# core09e.net
KiCad netlist of a schematic drawn in EAGLE
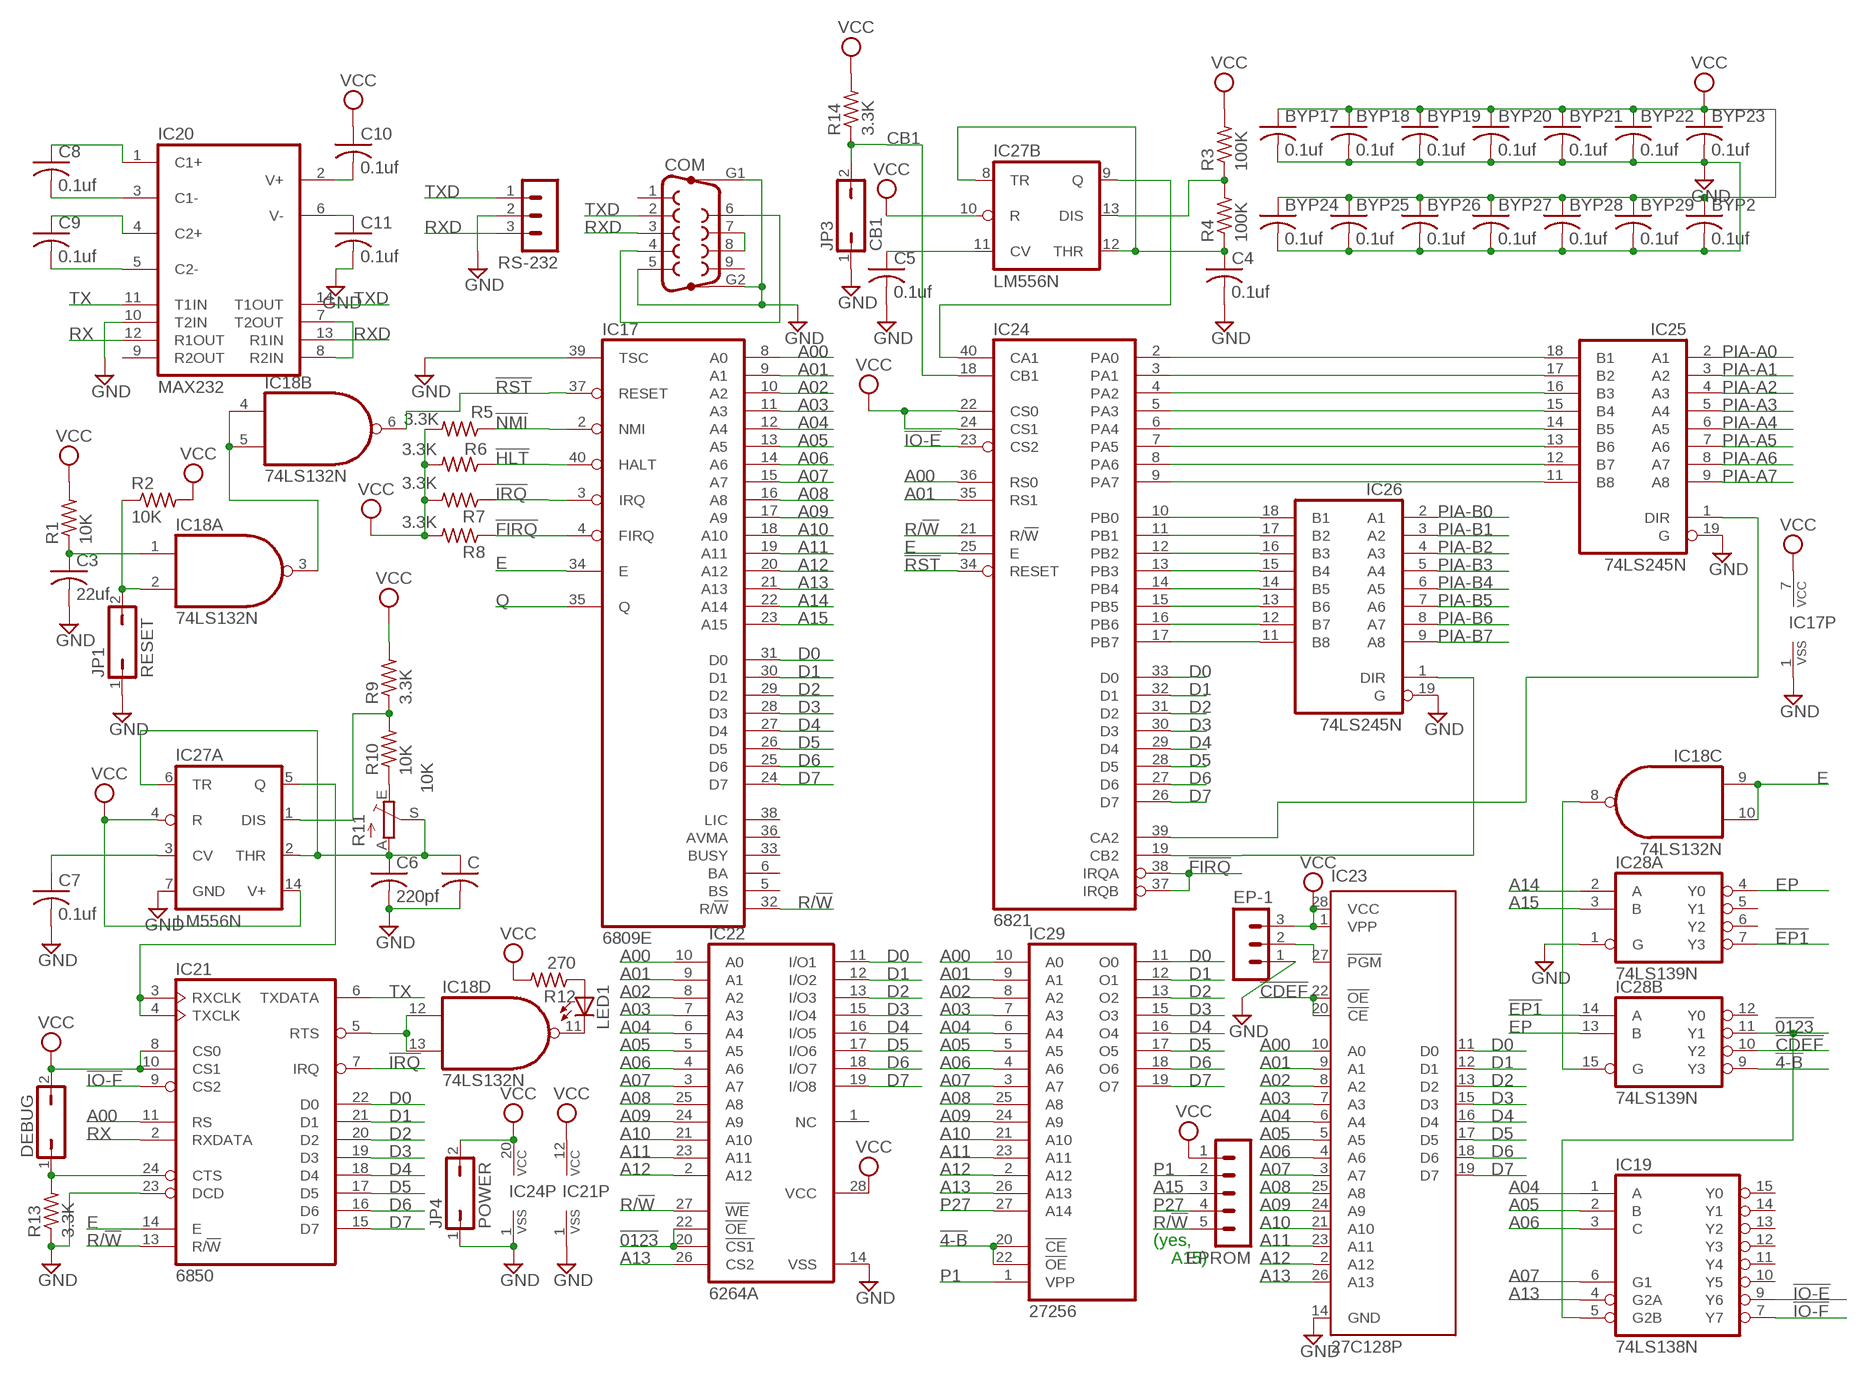
[diagram p0: schematic, sheet 1]
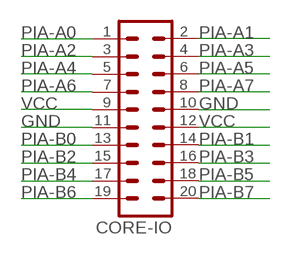
[diagram p1: schematic, sheet 2]
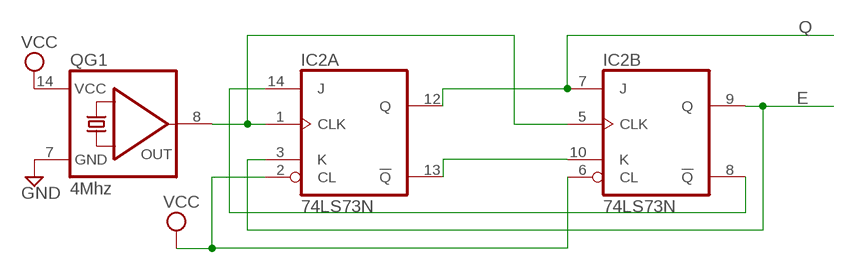
[diagram p2: schematic, sheet 3]

(export (version "E")
  (design (tool "Eeschema 10.0.6"))
  (components
    (comp (ref "IC2")
      (value "74LS73N")
      (footprint "eagle-import:DIL14")
      (libsource (lib "eagle-import") (part "7473NLS"))
    )
    (comp (ref "QG1")
      (value "4Mhz")
      (footprint "eagle-import:DIL14S")
      (libsource (lib "eagle-import") (part "QG5860"))
    )
    (comp (ref "BYP2")
      (value "0.1uf")
      (footprint "eagle-import:C050-025X075")
      (libsource (lib "eagle-import") (part "C-US050-025X075"))
    )
    (comp (ref "BYP17")
      (value "0.1uf")
      (footprint "eagle-import:C050-025X075")
      (libsource (lib "eagle-import") (part "C-US050-025X075"))
    )
    (comp (ref "BYP18")
      (value "0.1uf")
      (footprint "eagle-import:C050-025X075")
      (libsource (lib "eagle-import") (part "C-US050-025X075"))
    )
    (comp (ref "BYP19")
      (value "0.1uf")
      (footprint "eagle-import:C050-025X075")
      (libsource (lib "eagle-import") (part "C-US050-025X075"))
    )
    (comp (ref "BYP20")
      (value "0.1uf")
      (footprint "eagle-import:C050-025X075")
      (libsource (lib "eagle-import") (part "C-US050-025X075"))
    )
    (comp (ref "BYP21")
      (value "0.1uf")
      (footprint "eagle-import:C050-025X075")
      (libsource (lib "eagle-import") (part "C-US050-025X075"))
    )
    (comp (ref "BYP22")
      (value "0.1uf")
      (footprint "eagle-import:C050-025X075")
      (libsource (lib "eagle-import") (part "C-US050-025X075"))
    )
    (comp (ref "BYP23")
      (value "0.1uf")
      (footprint "eagle-import:C050-025X075")
      (libsource (lib "eagle-import") (part "C-US050-025X075"))
    )
    (comp (ref "BYP24")
      (value "0.1uf")
      (footprint "eagle-import:C050-025X075")
      (libsource (lib "eagle-import") (part "C-US050-025X075"))
    )
    (comp (ref "BYP25")
      (value "0.1uf")
      (footprint "eagle-import:C050-025X075")
      (libsource (lib "eagle-import") (part "C-US050-025X075"))
    )
    (comp (ref "BYP26")
      (value "0.1uf")
      (footprint "eagle-import:C050-025X075")
      (libsource (lib "eagle-import") (part "C-US050-025X075"))
    )
    (comp (ref "BYP27")
      (value "0.1uf")
      (footprint "eagle-import:C050-025X075")
      (libsource (lib "eagle-import") (part "C-US050-025X075"))
    )
    (comp (ref "BYP28")
      (value "0.1uf")
      (footprint "eagle-import:C050-025X075")
      (libsource (lib "eagle-import") (part "C-US050-025X075"))
    )
    (comp (ref "BYP29")
      (value "0.1uf")
      (footprint "eagle-import:C050-025X075")
      (libsource (lib "eagle-import") (part "C-US050-025X075"))
    )
    (comp (ref "C")
      (value "C-US050-025X075")
      (footprint "eagle-import:C050-025X075")
      (libsource (lib "eagle-import") (part "C-US050-025X075"))
    )
    (comp (ref "C3")
      (value "22uf")
      (footprint "eagle-import:C102-054X133")
      (libsource (lib "eagle-import") (part "C-US102-054X133"))
    )
    (comp (ref "C4")
      (value "0.1uf")
      (footprint "eagle-import:C050-025X075")
      (libsource (lib "eagle-import") (part "C-US050-025X075"))
    )
    (comp (ref "C5")
      (value "0.1uf")
      (footprint "eagle-import:C050-025X075")
      (libsource (lib "eagle-import") (part "C-US050-025X075"))
    )
    (comp (ref "C6")
      (value "220pf")
      (footprint "eagle-import:C050-025X075")
      (libsource (lib "eagle-import") (part "C-US050-025X075"))
    )
    (comp (ref "C7")
      (value "0.1uf")
      (footprint "eagle-import:C050-025X075")
      (libsource (lib "eagle-import") (part "C-US050-025X075"))
    )
    (comp (ref "C8")
      (value "0.1uf")
      (footprint "eagle-import:C050-025X075")
      (libsource (lib "eagle-import") (part "C-US050-025X075"))
    )
    (comp (ref "C9")
      (value "0.1uf")
      (footprint "eagle-import:C050-025X075")
      (libsource (lib "eagle-import") (part "C-US050-025X075"))
    )
    (comp (ref "C10")
      (value "0.1uf")
      (footprint "eagle-import:C050-025X075")
      (libsource (lib "eagle-import") (part "C-US050-025X075"))
    )
    (comp (ref "C11")
      (value "0.1uf")
      (footprint "eagle-import:C050-025X075")
      (libsource (lib "eagle-import") (part "C-US050-025X075"))
    )
    (comp (ref "COM")
      (value "F09HP")
      (footprint "eagle-import:F09HP")
      (libsource (lib "eagle-import") (part "F09HP"))
    )
    (comp (ref "DEBUG")
      (value "JP1Q")
      (footprint "eagle-import:JP1")
      (libsource (lib "eagle-import") (part "JP1Q"))
    )
    (comp (ref "EP-1")
      (value "MA03-1")
      (footprint "eagle-import:MA03-1")
      (libsource (lib "eagle-import") (part "MA03-1"))
    )
    (comp (ref "EPROM")
      (value "MA05-1")
      (footprint "eagle-import:MA05-1")
      (libsource (lib "eagle-import") (part "MA05-1"))
    )
    (comp (ref "IC17")
      (value "6809E")
      (footprint "eagle-import:DIL40")
      (fields (field (name "MF") "NTE ELECTRONICS") (field (name "MPN") "NTE6809E"))
      (libsource (lib "eagle-import") (part "6809E"))
    )
    (comp (ref "IC18")
      (value "74LS132N")
      (footprint "eagle-import:DIL14")
      (libsource (lib "eagle-import") (part "7400NLS"))
    )
    (comp (ref "IC19")
      (value "74LS138N")
      (footprint "eagle-import:DIL16")
      (libsource (lib "eagle-import") (part "74138NLS"))
    )
    (comp (ref "IC20")
      (value "MAX232")
      (footprint "eagle-import:DIL16")
      (fields (field (name "MF") "MAXIM") (field (name "MPN") "MAX232ACPE+"))
      (libsource (lib "eagle-import") (part "MAX232"))
    )
    (comp (ref "IC21")
      (value "6850")
      (footprint "eagle-import:DIL24")
      (fields (field (name "MF") "NTE ELECTRONICS") (field (name "MPN") "NTE6850"))
      (libsource (lib "eagle-import") (part "6850"))
    )
    (comp (ref "IC22")
      (value "6264A")
      (footprint "eagle-import:DIL28-6")
      (libsource (lib "eagle-import") (part "6264A"))
    )
    (comp (ref "IC23")
      (value "27C128P")
      (footprint "eagle-import:DIL28-6")
      (libsource (lib "eagle-import") (part "27128PC"))
    )
    (comp (ref "IC24")
      (value "6821")
      (footprint "eagle-import:DIL40")
      (fields (field (name "MF") "NTE ELECTRONICS") (field (name "MPN") "NTE6821"))
      (libsource (lib "eagle-import") (part "6821"))
    )
    (comp (ref "IC25")
      (value "74LS245N")
      (footprint "eagle-import:DIL20")
      (libsource (lib "eagle-import") (part "74245NLS"))
    )
    (comp (ref "IC26")
      (value "74LS245N")
      (footprint "eagle-import:DIL20")
      (libsource (lib "eagle-import") (part "74245NLS"))
    )
    (comp (ref "IC27")
      (value "LM556N")
      (footprint "eagle-import:DIL14")
      (libsource (lib "eagle-import") (part "556NLM"))
    )
    (comp (ref "IC28")
      (value "74LS139N")
      (footprint "eagle-import:DIL16")
      (libsource (lib "eagle-import") (part "74139NLS"))
    )
    (comp (ref "IC29")
      (value "27256")
      (footprint "eagle-import:DIL28")
      (libsource (lib "eagle-import") (part "27256"))
    )
    (comp (ref "JP1")
      (value "RESET")
      (footprint "eagle-import:JP1")
      (libsource (lib "eagle-import") (part "JP1Q"))
    )
    (comp (ref "JP3")
      (value "CB1")
      (footprint "eagle-import:JP1")
      (libsource (lib "eagle-import") (part "JP1Q"))
    )
    (comp (ref "JP4")
      (value "POWER")
      (footprint "eagle-import:JP1")
      (libsource (lib "eagle-import") (part "JP1Q"))
    )
    (comp (ref "LED1")
      (value "LED3MM")
      (footprint "eagle-import:LED3MM")
      (libsource (lib "eagle-import") (part "LED3MM"))
    )
    (comp (ref "R1")
      (value "10K")
      (footprint "eagle-import:0207_7")
      (libsource (lib "eagle-import") (part "R-US_0207/7"))
    )
    (comp (ref "R2")
      (value "10K")
      (footprint "eagle-import:0207_7")
      (libsource (lib "eagle-import") (part "R-US_0207/7"))
    )
    (comp (ref "R3")
      (value "100K")
      (footprint "eagle-import:0207_7")
      (libsource (lib "eagle-import") (part "R-US_0207/7"))
    )
    (comp (ref "R4")
      (value "100K")
      (footprint "eagle-import:0207_7")
      (libsource (lib "eagle-import") (part "R-US_0207/7"))
    )
    (comp (ref "R5")
      (value "3.3K")
      (footprint "eagle-import:0207_7")
      (libsource (lib "eagle-import") (part "R-US_0207/7"))
    )
    (comp (ref "R6")
      (value "3.3K")
      (footprint "eagle-import:0207_7")
      (libsource (lib "eagle-import") (part "R-US_0207/7"))
    )
    (comp (ref "R7")
      (value "3.3K")
      (footprint "eagle-import:0207_7")
      (libsource (lib "eagle-import") (part "R-US_0207/7"))
    )
    (comp (ref "R8")
      (value "3.3K")
      (footprint "eagle-import:0207_7")
      (libsource (lib "eagle-import") (part "R-US_0207/7"))
    )
    (comp (ref "R9")
      (value "3.3K")
      (footprint "eagle-import:0207_7")
      (libsource (lib "eagle-import") (part "R-US_0207/7"))
    )
    (comp (ref "R10")
      (value "10K")
      (footprint "eagle-import:0207_7")
      (libsource (lib "eagle-import") (part "R-US_0207/7"))
    )
    (comp (ref "R11")
      (value "10K")
      (footprint "eagle-import:SP19L")
      (libsource (lib "eagle-import") (part "TRIM_EU-B90P"))
    )
    (comp (ref "R12")
      (value "270")
      (footprint "eagle-import:0207_7")
      (libsource (lib "eagle-import") (part "R-US_0207/7"))
    )
    (comp (ref "R13")
      (value "3.3K")
      (footprint "eagle-import:0207_7")
      (libsource (lib "eagle-import") (part "R-US_0207/7"))
    )
    (comp (ref "R14")
      (value "3.3K")
      (footprint "eagle-import:0207_7")
      (libsource (lib "eagle-import") (part "R-US_0207/7"))
    )
    (comp (ref "RS-232")
      (value "MA03-1")
      (footprint "eagle-import:MA03-1")
      (libsource (lib "eagle-import") (part "MA03-1"))
    )
    (comp (ref "CORE-IO")
      (value "MA10-2")
      (footprint "eagle-import:MA10-2")
      (libsource (lib "eagle-import") (part "MA10-2"))
    )
  )
  (nets
    (net (code "1") (name "A00") (class "Default")
      (node (ref "IC17") (pin "8") (pinfunction "A0_8") (pintype "tri_state"))
      (node (ref "IC21") (pin "11") (pinfunction "RS_11") (pintype "input"))
      (node (ref "IC22") (pin "10") (pinfunction "A0_10") (pintype "input"))
      (node (ref "IC23") (pin "10") (pinfunction "A0_10") (pintype "input"))
      (node (ref "IC24") (pin "36") (pinfunction "RS0_36") (pintype "input"))
      (node (ref "IC29") (pin "10") (pinfunction "A0_10") (pintype "input"))
    )
    (net (code "2") (name "A01") (class "Default")
      (node (ref "IC17") (pin "9") (pinfunction "A1_9") (pintype "tri_state"))
      (node (ref "IC22") (pin "9") (pinfunction "A1_9") (pintype "input"))
      (node (ref "IC23") (pin "9") (pinfunction "A1_9") (pintype "input"))
      (node (ref "IC24") (pin "35") (pinfunction "RS1_35") (pintype "input"))
      (node (ref "IC29") (pin "9") (pinfunction "A1_9") (pintype "input"))
    )
    (net (code "3") (name "A02") (class "Default")
      (node (ref "IC17") (pin "10") (pinfunction "A2_10") (pintype "tri_state"))
      (node (ref "IC22") (pin "8") (pinfunction "A2_8") (pintype "input"))
      (node (ref "IC23") (pin "8") (pinfunction "A2_8") (pintype "input"))
      (node (ref "IC29") (pin "8") (pinfunction "A2_8") (pintype "input"))
    )
    (net (code "4") (name "A03") (class "Default")
      (node (ref "IC17") (pin "11") (pinfunction "A3_11") (pintype "tri_state"))
      (node (ref "IC22") (pin "7") (pinfunction "A3_7") (pintype "input"))
      (node (ref "IC23") (pin "7") (pinfunction "A3_7") (pintype "input"))
      (node (ref "IC29") (pin "7") (pinfunction "A3_7") (pintype "input"))
    )
    (net (code "5") (name "A04") (class "Default")
      (node (ref "IC17") (pin "12") (pinfunction "A4_12") (pintype "tri_state"))
      (node (ref "IC19") (pin "1") (pinfunction "A_1") (pintype "input"))
      (node (ref "IC22") (pin "6") (pinfunction "A4_6") (pintype "input"))
      (node (ref "IC23") (pin "6") (pinfunction "A4_6") (pintype "input"))
      (node (ref "IC29") (pin "6") (pinfunction "A4_6") (pintype "input"))
    )
    (net (code "6") (name "A05") (class "Default")
      (node (ref "IC17") (pin "13") (pinfunction "A5_13") (pintype "tri_state"))
      (node (ref "IC19") (pin "2") (pinfunction "B_2") (pintype "input"))
      (node (ref "IC22") (pin "5") (pinfunction "A5_5") (pintype "input"))
      (node (ref "IC23") (pin "5") (pinfunction "A5_5") (pintype "input"))
      (node (ref "IC29") (pin "5") (pinfunction "A5_5") (pintype "input"))
    )
    (net (code "7") (name "A06") (class "Default")
      (node (ref "IC17") (pin "14") (pinfunction "A6_14") (pintype "tri_state"))
      (node (ref "IC19") (pin "3") (pinfunction "C_3") (pintype "input"))
      (node (ref "IC22") (pin "4") (pinfunction "A6_4") (pintype "input"))
      (node (ref "IC23") (pin "4") (pinfunction "A6_4") (pintype "input"))
      (node (ref "IC29") (pin "4") (pinfunction "A6_4") (pintype "input"))
    )
    (net (code "8") (name "A07") (class "Default")
      (node (ref "IC17") (pin "15") (pinfunction "A7_15") (pintype "tri_state"))
      (node (ref "IC19") (pin "6") (pinfunction "G1_6") (pintype "input"))
      (node (ref "IC22") (pin "3") (pinfunction "A7_3") (pintype "input"))
      (node (ref "IC23") (pin "3") (pinfunction "A7_3") (pintype "input"))
      (node (ref "IC29") (pin "3") (pinfunction "A7_3") (pintype "input"))
    )
    (net (code "9") (name "A08") (class "Default")
      (node (ref "IC17") (pin "16") (pinfunction "A8_16") (pintype "tri_state"))
      (node (ref "IC22") (pin "25") (pinfunction "A8_25") (pintype "input"))
      (node (ref "IC23") (pin "25") (pinfunction "A8_25") (pintype "input"))
      (node (ref "IC29") (pin "25") (pinfunction "A8_25") (pintype "input"))
    )
    (net (code "10") (name "A09") (class "Default")
      (node (ref "IC17") (pin "17") (pinfunction "A9_17") (pintype "tri_state"))
      (node (ref "IC22") (pin "24") (pinfunction "A9_24") (pintype "input"))
      (node (ref "IC23") (pin "24") (pinfunction "A9_24") (pintype "input"))
      (node (ref "IC29") (pin "24") (pinfunction "A9_24") (pintype "input"))
    )
    (net (code "11") (name "A10") (class "Default")
      (node (ref "IC17") (pin "18") (pinfunction "A10_18") (pintype "tri_state"))
      (node (ref "IC22") (pin "21") (pinfunction "A10_21") (pintype "input"))
      (node (ref "IC23") (pin "21") (pinfunction "A10_21") (pintype "input"))
      (node (ref "IC29") (pin "21") (pinfunction "A10_21") (pintype "input"))
    )
    (net (code "12") (name "A11") (class "Default")
      (node (ref "IC17") (pin "19") (pinfunction "A11_19") (pintype "tri_state"))
      (node (ref "IC22") (pin "23") (pinfunction "A11_23") (pintype "input"))
      (node (ref "IC23") (pin "23") (pinfunction "A11_23") (pintype "input"))
      (node (ref "IC29") (pin "23") (pinfunction "A11_23") (pintype "input"))
    )
    (net (code "13") (name "A12") (class "Default")
      (node (ref "IC17") (pin "20") (pinfunction "A12_20") (pintype "tri_state"))
      (node (ref "IC22") (pin "2") (pinfunction "A12_2") (pintype "input"))
      (node (ref "IC23") (pin "2") (pinfunction "A12_2") (pintype "input"))
      (node (ref "IC29") (pin "2") (pinfunction "A12_2") (pintype "input"))
    )
    (net (code "14") (name "A13") (class "Default")
      (node (ref "IC17") (pin "21") (pinfunction "A13_21") (pintype "tri_state"))
      (node (ref "IC19") (pin "4") (pinfunction "G2A_4") (pintype "input"))
      (node (ref "IC22") (pin "26") (pinfunction "CS2_26") (pintype "input"))
      (node (ref "IC23") (pin "26") (pinfunction "A13_26") (pintype "input"))
      (node (ref "IC29") (pin "26") (pinfunction "A13_26") (pintype "input"))
    )
    (net (code "15") (name "A14") (class "Default")
      (node (ref "IC17") (pin "22") (pinfunction "A14_22") (pintype "tri_state"))
      (node (ref "IC28") (pin "2") (pinfunction "A_2") (pintype "input"))
    )
    (net (code "16") (name "A15") (class "Default")
      (node (ref "EPROM") (pin "3") (pinfunction "3_3") (pintype "passive"))
      (node (ref "IC17") (pin "23") (pinfunction "A15_23") (pintype "tri_state"))
      (node (ref "IC28") (pin "3") (pinfunction "B_3") (pintype "input"))
    )
    (net (code "17") (name "CB1") (class "Default")
      (node (ref "IC24") (pin "18") (pinfunction "CB1_18") (pintype "input"))
      (node (ref "JP3") (pin "2") (pinfunction "2_2") (pintype "passive"))
      (node (ref "R14") (pin "1") (pinfunction "1_1") (pintype "passive"))
    )
    (net (code "18") (name "D0") (class "Default")
      (node (ref "IC17") (pin "31") (pinfunction "D0_31") (pintype "bidirectional"))
      (node (ref "IC21") (pin "22") (pinfunction "D0_22") (pintype "bidirectional"))
      (node (ref "IC22") (pin "11") (pinfunction "I/O1_11") (pintype "bidirectional"))
      (node (ref "IC23") (pin "11") (pinfunction "D0_11") (pintype "tri_state"))
      (node (ref "IC24") (pin "33") (pinfunction "D0_33") (pintype "bidirectional"))
      (node (ref "IC29") (pin "11") (pinfunction "O0_11") (pintype "tri_state"))
    )
    (net (code "19") (name "D1") (class "Default")
      (node (ref "IC17") (pin "30") (pinfunction "D1_30") (pintype "bidirectional"))
      (node (ref "IC21") (pin "21") (pinfunction "D1_21") (pintype "bidirectional"))
      (node (ref "IC22") (pin "12") (pinfunction "I/O2_12") (pintype "bidirectional"))
      (node (ref "IC23") (pin "12") (pinfunction "D1_12") (pintype "tri_state"))
      (node (ref "IC24") (pin "32") (pinfunction "D1_32") (pintype "bidirectional"))
      (node (ref "IC29") (pin "12") (pinfunction "O1_12") (pintype "tri_state"))
    )
    (net (code "20") (name "D2") (class "Default")
      (node (ref "IC17") (pin "29") (pinfunction "D2_29") (pintype "bidirectional"))
      (node (ref "IC21") (pin "20") (pinfunction "D2_20") (pintype "bidirectional"))
      (node (ref "IC22") (pin "13") (pinfunction "I/O3_13") (pintype "bidirectional"))
      (node (ref "IC23") (pin "13") (pinfunction "D2_13") (pintype "tri_state"))
      (node (ref "IC24") (pin "31") (pinfunction "D2_31") (pintype "bidirectional"))
      (node (ref "IC29") (pin "13") (pinfunction "O2_13") (pintype "tri_state"))
    )
    (net (code "21") (name "D3") (class "Default")
      (node (ref "IC17") (pin "28") (pinfunction "D3_28") (pintype "bidirectional"))
      (node (ref "IC21") (pin "19") (pinfunction "D3_19") (pintype "bidirectional"))
      (node (ref "IC22") (pin "15") (pinfunction "I/O4_15") (pintype "bidirectional"))
      (node (ref "IC23") (pin "15") (pinfunction "D3_15") (pintype "tri_state"))
      (node (ref "IC24") (pin "30") (pinfunction "D3_30") (pintype "bidirectional"))
      (node (ref "IC29") (pin "15") (pinfunction "O3_15") (pintype "tri_state"))
    )
    (net (code "22") (name "D4") (class "Default")
      (node (ref "IC17") (pin "27") (pinfunction "D4_27") (pintype "bidirectional"))
      (node (ref "IC21") (pin "18") (pinfunction "D4_18") (pintype "bidirectional"))
      (node (ref "IC22") (pin "16") (pinfunction "I/O5_16") (pintype "bidirectional"))
      (node (ref "IC23") (pin "16") (pinfunction "D4_16") (pintype "tri_state"))
      (node (ref "IC24") (pin "29") (pinfunction "D4_29") (pintype "bidirectional"))
      (node (ref "IC29") (pin "16") (pinfunction "O4_16") (pintype "tri_state"))
    )
    (net (code "23") (name "D5") (class "Default")
      (node (ref "IC17") (pin "26") (pinfunction "D5_26") (pintype "bidirectional"))
      (node (ref "IC21") (pin "17") (pinfunction "D5_17") (pintype "bidirectional"))
      (node (ref "IC22") (pin "17") (pinfunction "I/O6_17") (pintype "bidirectional"))
      (node (ref "IC23") (pin "17") (pinfunction "D5_17") (pintype "tri_state"))
      (node (ref "IC24") (pin "28") (pinfunction "D5_28") (pintype "bidirectional"))
      (node (ref "IC29") (pin "17") (pinfunction "O5_17") (pintype "tri_state"))
    )
    (net (code "24") (name "D6") (class "Default")
      (node (ref "IC17") (pin "25") (pinfunction "D6_25") (pintype "bidirectional"))
      (node (ref "IC21") (pin "16") (pinfunction "D6_16") (pintype "bidirectional"))
      (node (ref "IC22") (pin "18") (pinfunction "I/O7_18") (pintype "bidirectional"))
      (node (ref "IC23") (pin "18") (pinfunction "D6_18") (pintype "tri_state"))
      (node (ref "IC24") (pin "27") (pinfunction "D6_27") (pintype "bidirectional"))
      (node (ref "IC29") (pin "18") (pinfunction "O6_18") (pintype "tri_state"))
    )
    (net (code "25") (name "D7") (class "Default")
      (node (ref "IC17") (pin "24") (pinfunction "D7_24") (pintype "bidirectional"))
      (node (ref "IC21") (pin "15") (pinfunction "D7_15") (pintype "bidirectional"))
      (node (ref "IC22") (pin "19") (pinfunction "I/O8_19") (pintype "bidirectional"))
      (node (ref "IC23") (pin "19") (pinfunction "D7_19") (pintype "tri_state"))
      (node (ref "IC24") (pin "26") (pinfunction "D7_26") (pintype "bidirectional"))
      (node (ref "IC29") (pin "19") (pinfunction "O7_19") (pintype "tri_state"))
    )
    (net (code "26") (name "E") (class "Default")
      (node (ref "IC17") (pin "34") (pinfunction "E_34") (pintype "input"))
      (node (ref "IC18") (pin "10") (pinfunction "I1_10") (pintype "input"))
      (node (ref "IC18") (pin "9") (pinfunction "I0_9") (pintype "input"))
      (node (ref "IC2") (pin "3") (pinfunction "K_3") (pintype "input"))
      (node (ref "IC2") (pin "9") (pinfunction "Q_9") (pintype "output"))
      (node (ref "IC21") (pin "14") (pinfunction "E_14") (pintype "input"))
      (node (ref "IC24") (pin "25") (pinfunction "E_25") (pintype "input"))
    )
    (net (code "27") (name "EP") (class "Default")
      (node (ref "IC28") (pin "13") (pinfunction "B_13") (pintype "input"))
      (node (ref "IC28") (pin "4") (pinfunction "Y0_4") (pintype "output"))
    )
    (net (code "28") (name "GND") (class "Default")
      (node (ref "BYP17") (pin "2") (pinfunction "2_2") (pintype "passive"))
      (node (ref "BYP18") (pin "2") (pinfunction "2_2") (pintype "passive"))
      (node (ref "BYP19") (pin "2") (pinfunction "2_2") (pintype "passive"))
      (node (ref "BYP2") (pin "2") (pinfunction "2_2") (pintype "passive"))
      (node (ref "BYP20") (pin "2") (pinfunction "2_2") (pintype "passive"))
      (node (ref "BYP21") (pin "2") (pinfunction "2_2") (pintype "passive"))
      (node (ref "BYP22") (pin "2") (pinfunction "2_2") (pintype "passive"))
      (node (ref "BYP23") (pin "2") (pinfunction "2_2") (pintype "passive"))
      (node (ref "BYP24") (pin "2") (pinfunction "2_2") (pintype "passive"))
      (node (ref "BYP25") (pin "2") (pinfunction "2_2") (pintype "passive"))
      (node (ref "BYP26") (pin "2") (pinfunction "2_2") (pintype "passive"))
      (node (ref "BYP27") (pin "2") (pinfunction "2_2") (pintype "passive"))
      (node (ref "BYP28") (pin "2") (pinfunction "2_2") (pintype "passive"))
      (node (ref "BYP29") (pin "2") (pinfunction "2_2") (pintype "passive"))
      (node (ref "C") (pin "2") (pinfunction "2_2") (pintype "passive"))
      (node (ref "C11") (pin "2") (pinfunction "2_2") (pintype "passive"))
      (node (ref "C3") (pin "2") (pinfunction "2_2") (pintype "passive"))
      (node (ref "C4") (pin "2") (pinfunction "2_2") (pintype "passive"))
      (node (ref "C5") (pin "2") (pinfunction "2_2") (pintype "passive"))
      (node (ref "C6") (pin "2") (pinfunction "2_2") (pintype "passive"))
      (node (ref "C7") (pin "2") (pinfunction "2_2") (pintype "passive"))
      (node (ref "COM") (pin "5") (pinfunction "5_5") (pintype "passive"))
      (node (ref "COM") (pin "G1") (pinfunction "G1_G1") (pintype "passive"))
      (node (ref "COM") (pin "G2") (pinfunction "G2_G2") (pintype "passive"))
      (node (ref "CORE-IO") (pin "10") (pinfunction "10_10") (pintype "passive"))
      (node (ref "CORE-IO") (pin "11") (pinfunction "11_11") (pintype "passive"))
      (node (ref "EP-1") (pin "1") (pinfunction "1_1") (pintype "passive"))
      (node (ref "IC17") (pin "1") (pinfunction "VSS_1") (pintype "power_in"))
      (node (ref "IC17") (pin "39") (pinfunction "TSC_39") (pintype "input"))
      (node (ref "IC20") (pin "10") (pinfunction "T2IN_10") (pintype "input"))
      (node (ref "IC21") (pin "1") (pinfunction "VSS_1") (pintype "power_in"))
      (node (ref "IC21") (pin "23") (pinfunction "DCD_23") (pintype "input"))
      (node (ref "IC22") (pin "14") (pinfunction "VSS_14") (pintype "power_in"))
      (node (ref "IC23") (pin "14") (pinfunction "GND_14") (pintype "power_in"))
      (node (ref "IC24") (pin "1") (pinfunction "VSS_1") (pintype "power_in"))
      (node (ref "IC25") (pin "19") (pinfunction "G_19") (pintype "input"))
      (node (ref "IC26") (pin "19") (pinfunction "G_19") (pintype "input"))
      (node (ref "IC27") (pin "7") (pinfunction "GND_7") (pintype "power_in"))
      (node (ref "IC28") (pin "1") (pinfunction "G_1") (pintype "input"))
      (node (ref "JP1") (pin "1") (pinfunction "1_1") (pintype "passive"))
      (node (ref "JP3") (pin "1") (pinfunction "1_1") (pintype "passive"))
      (node (ref "JP4") (pin "1") (pinfunction "1_1") (pintype "passive"))
      (node (ref "QG1") (pin "7") (pinfunction "GND_7") (pintype "power_in"))
      (node (ref "R13") (pin "1") (pinfunction "1_1") (pintype "passive"))
      (node (ref "RS-232") (pin "2") (pinfunction "2_2") (pintype "passive"))
    )
    (net (code "29") (name "Net-(COM-Pad4)") (class "Default")
      (node (ref "COM") (pin "4") (pinfunction "4_4") (pintype "passive"))
      (node (ref "COM") (pin "6") (pinfunction "6_6") (pintype "passive"))
    )
    (net (code "30") (name "Net-(COM-Pad7)") (class "Default")
      (node (ref "COM") (pin "7") (pinfunction "7_7") (pintype "passive"))
      (node (ref "COM") (pin "8") (pinfunction "8_8") (pintype "passive"))
    )
    (net (code "31") (name "Net-(IC2A-CLK)") (class "Default")
      (node (ref "IC2") (pin "1") (pinfunction "CLK_1") (pintype "input"))
      (node (ref "IC2") (pin "5") (pinfunction "CLK_5") (pintype "input"))
      (node (ref "QG1") (pin "8") (pinfunction "OUT_8") (pintype "output"))
    )
    (net (code "32") (name "Net-(IC2A-J)") (class "Default")
      (node (ref "IC2") (pin "14") (pinfunction "J_14") (pintype "input"))
      (node (ref "IC2") (pin "8") (pinfunction "~{Q}_8") (pintype "output"))
    )
    (net (code "33") (name "Net-(IC2A-~{Q})") (class "Default")
      (node (ref "IC2") (pin "10") (pinfunction "K_10") (pintype "input"))
      (node (ref "IC2") (pin "13") (pinfunction "~{Q}_13") (pintype "output"))
    )
    (net (code "34") (name "Net-(IC18A-I0)") (class "Default")
      (node (ref "C3") (pin "1") (pinfunction "1_1") (pintype "passive"))
      (node (ref "IC18") (pin "1") (pinfunction "I0_1") (pintype "input"))
      (node (ref "R1") (pin "1") (pinfunction "1_1") (pintype "passive"))
    )
    (net (code "35") (name "Net-(IC18A-I1)") (class "Default")
      (node (ref "IC18") (pin "2") (pinfunction "I1_2") (pintype "input"))
      (node (ref "JP1") (pin "2") (pinfunction "2_2") (pintype "passive"))
      (node (ref "R2") (pin "1") (pinfunction "1_1") (pintype "passive"))
    )
    (net (code "36") (name "Net-(IC18A-O)") (class "Default")
      (node (ref "IC18") (pin "3") (pinfunction "O_3") (pintype "output"))
      (node (ref "IC18") (pin "4") (pinfunction "I0_4") (pintype "input"))
      (node (ref "IC18") (pin "5") (pinfunction "I1_5") (pintype "input"))
    )
    (net (code "37") (name "Net-(IC18C-O)") (class "Default")
      (node (ref "IC18") (pin "8") (pinfunction "O_8") (pintype "output"))
      (node (ref "IC28") (pin "15") (pinfunction "G_15") (pintype "input"))
    )
    (net (code "38") (name "Net-(IC18D-I0)") (class "Default")
      (node (ref "IC18") (pin "12") (pinfunction "I0_12") (pintype "input"))
      (node (ref "IC18") (pin "13") (pinfunction "I1_13") (pintype "input"))
      (node (ref "IC21") (pin "5") (pinfunction "RTS_5") (pintype "output"))
    )
    (net (code "39") (name "Net-(IC18D-O)") (class "Default")
      (node (ref "IC18") (pin "11") (pinfunction "O_11") (pintype "output"))
      (node (ref "LED1") (pin "K") (pinfunction "C_K") (pintype "passive"))
    )
    (net (code "40") (name "Net-(IC20A-C1+)") (class "Default")
      (node (ref "C8") (pin "1") (pinfunction "1_1") (pintype "passive"))
      (node (ref "IC20") (pin "1") (pinfunction "C1+_1") (pintype "bidirectional"))
    )
    (net (code "41") (name "Net-(IC20A-C1-)") (class "Default")
      (node (ref "C8") (pin "2") (pinfunction "2_2") (pintype "passive"))
      (node (ref "IC20") (pin "3") (pinfunction "C1-_3") (pintype "bidirectional"))
    )
    (net (code "42") (name "Net-(IC20A-C2+)") (class "Default")
      (node (ref "C9") (pin "1") (pinfunction "1_1") (pintype "passive"))
      (node (ref "IC20") (pin "4") (pinfunction "C2+_4") (pintype "bidirectional"))
    )
    (net (code "43") (name "Net-(IC20A-C2-)") (class "Default")
      (node (ref "C9") (pin "2") (pinfunction "2_2") (pintype "passive"))
      (node (ref "IC20") (pin "5") (pinfunction "C2-_5") (pintype "bidirectional"))
    )
    (net (code "44") (name "Net-(IC20A-R2IN)") (class "Default")
      (node (ref "IC20") (pin "7") (pinfunction "T2OUT_7") (pintype "output"))
      (node (ref "IC20") (pin "8") (pinfunction "R2IN_8") (pintype "input"))
    )
    (net (code "45") (name "Net-(IC20A-V+)") (class "Default")
      (node (ref "C10") (pin "2") (pinfunction "2_2") (pintype "passive"))
      (node (ref "IC20") (pin "2") (pinfunction "V+_2") (pintype "bidirectional"))
    )
    (net (code "46") (name "Net-(IC20A-V-)") (class "Default")
      (node (ref "C11") (pin "1") (pinfunction "1_1") (pintype "passive"))
      (node (ref "IC20") (pin "6") (pinfunction "V-_6") (pintype "bidirectional"))
    )
    (net (code "47") (name "Net-(IC21A-CTS)") (class "Default")
      (node (ref "DEBUG") (pin "1") (pinfunction "1_1") (pintype "passive"))
      (node (ref "IC21") (pin "24") (pinfunction "CTS_24") (pintype "input"))
      (node (ref "R13") (pin "2") (pinfunction "2_2") (pintype "passive"))
    )
    (net (code "48") (name "Net-(IC21A-RXCLK)") (class "Default")
      (node (ref "IC21") (pin "3") (pinfunction "RXCLK_3") (pintype "input"))
      (node (ref "IC21") (pin "4") (pinfunction "TXCLK_4") (pintype "input"))
      (node (ref "IC27") (pin "5") (pinfunction "Q_5") (pintype "output"))
    )
    (net (code "49") (name "Net-(IC23-~{PGM})") (class "Default")
      (node (ref "EP-1") (pin "2") (pinfunction "2_2") (pintype "passive"))
      (node (ref "IC23") (pin "27") (pinfunction "~{PGM}_27") (pintype "passive"))
    )
    (net (code "50") (name "Net-(IC24A-CA1)") (class "Default")
      (node (ref "IC24") (pin "40") (pinfunction "CA1_40") (pintype "input"))
      (node (ref "IC27") (pin "9") (pinfunction "Q_9") (pintype "output"))
    )
    (net (code "51") (name "Net-(IC24A-CA2)") (class "Default")
      (node (ref "IC24") (pin "39") (pinfunction "CA2_39") (pintype "bidirectional"))
      (node (ref "IC25") (pin "1") (pinfunction "DIR_1") (pintype "input"))
    )
    (net (code "52") (name "Net-(IC24A-CB2)") (class "Default")
      (node (ref "IC24") (pin "19") (pinfunction "CB2_19") (pintype "bidirectional"))
      (node (ref "IC26") (pin "1") (pinfunction "DIR_1") (pintype "input"))
    )
    (net (code "53") (name "Net-(IC24A-PA0)") (class "Default")
      (node (ref "IC24") (pin "2") (pinfunction "PA0_2") (pintype "bidirectional"))
      (node (ref "IC25") (pin "18") (pinfunction "B1_18") (pintype "bidirectional"))
    )
    (net (code "54") (name "Net-(IC24A-PA1)") (class "Default")
      (node (ref "IC24") (pin "3") (pinfunction "PA1_3") (pintype "bidirectional"))
      (node (ref "IC25") (pin "17") (pinfunction "B2_17") (pintype "bidirectional"))
    )
    (net (code "55") (name "Net-(IC24A-PA2)") (class "Default")
      (node (ref "IC24") (pin "4") (pinfunction "PA2_4") (pintype "bidirectional"))
      (node (ref "IC25") (pin "16") (pinfunction "B3_16") (pintype "bidirectional"))
    )
    (net (code "56") (name "Net-(IC24A-PA3)") (class "Default")
      (node (ref "IC24") (pin "5") (pinfunction "PA3_5") (pintype "bidirectional"))
      (node (ref "IC25") (pin "15") (pinfunction "B4_15") (pintype "bidirectional"))
    )
    (net (code "57") (name "Net-(IC24A-PA4)") (class "Default")
      (node (ref "IC24") (pin "6") (pinfunction "PA4_6") (pintype "bidirectional"))
      (node (ref "IC25") (pin "14") (pinfunction "B5_14") (pintype "bidirectional"))
    )
    (net (code "58") (name "Net-(IC24A-PA5)") (class "Default")
      (node (ref "IC24") (pin "7") (pinfunction "PA5_7") (pintype "bidirectional"))
      (node (ref "IC25") (pin "13") (pinfunction "B6_13") (pintype "bidirectional"))
    )
    (net (code "59") (name "Net-(IC24A-PA6)") (class "Default")
      (node (ref "IC24") (pin "8") (pinfunction "PA6_8") (pintype "bidirectional"))
      (node (ref "IC25") (pin "12") (pinfunction "B7_12") (pintype "bidirectional"))
    )
    (net (code "60") (name "Net-(IC24A-PA7)") (class "Default")
      (node (ref "IC24") (pin "9") (pinfunction "PA7_9") (pintype "bidirectional"))
      (node (ref "IC25") (pin "11") (pinfunction "B8_11") (pintype "bidirectional"))
    )
    (net (code "61") (name "Net-(IC24A-PB0)") (class "Default")
      (node (ref "IC24") (pin "10") (pinfunction "PB0_10") (pintype "bidirectional"))
      (node (ref "IC26") (pin "18") (pinfunction "B1_18") (pintype "bidirectional"))
    )
    (net (code "62") (name "Net-(IC24A-PB1)") (class "Default")
      (node (ref "IC24") (pin "11") (pinfunction "PB1_11") (pintype "bidirectional"))
      (node (ref "IC26") (pin "17") (pinfunction "B2_17") (pintype "bidirectional"))
    )
    (net (code "63") (name "Net-(IC24A-PB2)") (class "Default")
      (node (ref "IC24") (pin "12") (pinfunction "PB2_12") (pintype "bidirectional"))
      (node (ref "IC26") (pin "16") (pinfunction "B3_16") (pintype "bidirectional"))
    )
    (net (code "64") (name "Net-(IC24A-PB3)") (class "Default")
      (node (ref "IC24") (pin "13") (pinfunction "PB3_13") (pintype "bidirectional"))
      (node (ref "IC26") (pin "15") (pinfunction "B4_15") (pintype "bidirectional"))
    )
    (net (code "65") (name "Net-(IC24A-PB4)") (class "Default")
      (node (ref "IC24") (pin "14") (pinfunction "PB4_14") (pintype "bidirectional"))
      (node (ref "IC26") (pin "14") (pinfunction "B5_14") (pintype "bidirectional"))
    )
    (net (code "66") (name "Net-(IC24A-PB5)") (class "Default")
      (node (ref "IC24") (pin "15") (pinfunction "PB5_15") (pintype "bidirectional"))
      (node (ref "IC26") (pin "13") (pinfunction "B6_13") (pintype "bidirectional"))
    )
    (net (code "67") (name "Net-(IC24A-PB6)") (class "Default")
      (node (ref "IC24") (pin "16") (pinfunction "PB6_16") (pintype "bidirectional"))
      (node (ref "IC26") (pin "12") (pinfunction "B7_12") (pintype "bidirectional"))
    )
    (net (code "68") (name "Net-(IC24A-PB7)") (class "Default")
      (node (ref "IC24") (pin "17") (pinfunction "PB7_17") (pintype "bidirectional"))
      (node (ref "IC26") (pin "11") (pinfunction "B8_11") (pintype "bidirectional"))
    )
    (net (code "69") (name "Net-(IC27A-CV)") (class "Default")
      (node (ref "C7") (pin "1") (pinfunction "1_1") (pintype "passive"))
      (node (ref "IC27") (pin "3") (pinfunction "CV_3") (pintype "input"))
    )
    (net (code "70") (name "Net-(IC27A-DIS)") (class "Default")
      (node (ref "IC27") (pin "1") (pinfunction "DIS_1") (pintype "input"))
      (node (ref "R10") (pin "2") (pinfunction "2_2") (pintype "passive"))
      (node (ref "R9") (pin "1") (pinfunction "1_1") (pintype "passive"))
    )
    (net (code "71") (name "Net-(IC27A-THR)") (class "Default")
      (node (ref "C") (pin "1") (pinfunction "1_1") (pintype "passive"))
      (node (ref "C6") (pin "1") (pinfunction "1_1") (pintype "passive"))
      (node (ref "IC27") (pin "2") (pinfunction "THR_2") (pintype "input"))
      (node (ref "IC27") (pin "6") (pinfunction "TR_6") (pintype "input"))
      (node (ref "R11") (pin "A") (pinfunction "A_A") (pintype "passive"))
      (node (ref "R11") (pin "S") (pinfunction "S_S") (pintype "passive"))
    )
    (net (code "72") (name "Net-(IC27B-CV)") (class "Default")
      (node (ref "C5") (pin "1") (pinfunction "1_1") (pintype "passive"))
      (node (ref "IC27") (pin "11") (pinfunction "CV_11") (pintype "input"))
    )
    (net (code "73") (name "Net-(IC27B-DIS)") (class "Default")
      (node (ref "IC27") (pin "13") (pinfunction "DIS_13") (pintype "input"))
      (node (ref "R3") (pin "1") (pinfunction "1_1") (pintype "passive"))
      (node (ref "R4") (pin "2") (pinfunction "2_2") (pintype "passive"))
    )
    (net (code "74") (name "Net-(IC27B-THR)") (class "Default")
      (node (ref "C4") (pin "1") (pinfunction "1_1") (pintype "passive"))
      (node (ref "IC27") (pin "12") (pinfunction "THR_12") (pintype "input"))
      (node (ref "IC27") (pin "8") (pinfunction "TR_8") (pintype "input"))
      (node (ref "R4") (pin "1") (pinfunction "1_1") (pintype "passive"))
    )
    (net (code "75") (name "Net-(LED1-PadA)") (class "Default")
      (node (ref "LED1") (pin "A") (pinfunction "A_A") (pintype "passive"))
      (node (ref "R12") (pin "1") (pinfunction "1_1") (pintype "passive"))
    )
    (net (code "76") (name "Net-(R10-Pad1)") (class "Default")
      (node (ref "R10") (pin "1") (pinfunction "1_1") (pintype "passive"))
      (node (ref "R11") (pin "E") (pinfunction "E_E") (pintype "passive"))
    )
    (net (code "77") (name "P1") (class "Default")
      (node (ref "EPROM") (pin "2") (pinfunction "2_2") (pintype "passive"))
      (node (ref "IC29") (pin "1") (pinfunction "VPP_1") (pintype "input"))
    )
    (net (code "78") (name "P27") (class "Default")
      (node (ref "EPROM") (pin "4") (pinfunction "4_4") (pintype "passive"))
      (node (ref "IC29") (pin "27") (pinfunction "A14_27") (pintype "input"))
    )
    (net (code "79") (name "PIA-A0") (class "Default")
      (node (ref "CORE-IO") (pin "1") (pinfunction "1_1") (pintype "passive"))
      (node (ref "IC25") (pin "2") (pinfunction "A1_2") (pintype "bidirectional"))
    )
    (net (code "80") (name "PIA-A1") (class "Default")
      (node (ref "CORE-IO") (pin "2") (pinfunction "2_2") (pintype "passive"))
      (node (ref "IC25") (pin "3") (pinfunction "A2_3") (pintype "bidirectional"))
    )
    (net (code "81") (name "PIA-A2") (class "Default")
      (node (ref "CORE-IO") (pin "3") (pinfunction "3_3") (pintype "passive"))
      (node (ref "IC25") (pin "4") (pinfunction "A3_4") (pintype "bidirectional"))
    )
    (net (code "82") (name "PIA-A3") (class "Default")
      (node (ref "CORE-IO") (pin "4") (pinfunction "4_4") (pintype "passive"))
      (node (ref "IC25") (pin "5") (pinfunction "A4_5") (pintype "bidirectional"))
    )
    (net (code "83") (name "PIA-A4") (class "Default")
      (node (ref "CORE-IO") (pin "5") (pinfunction "5_5") (pintype "passive"))
      (node (ref "IC25") (pin "6") (pinfunction "A5_6") (pintype "bidirectional"))
    )
    (net (code "84") (name "PIA-A5") (class "Default")
      (node (ref "CORE-IO") (pin "6") (pinfunction "6_6") (pintype "passive"))
      (node (ref "IC25") (pin "7") (pinfunction "A6_7") (pintype "bidirectional"))
    )
    (net (code "85") (name "PIA-A6") (class "Default")
      (node (ref "CORE-IO") (pin "7") (pinfunction "7_7") (pintype "passive"))
      (node (ref "IC25") (pin "8") (pinfunction "A7_8") (pintype "bidirectional"))
    )
    (net (code "86") (name "PIA-A7") (class "Default")
      (node (ref "CORE-IO") (pin "8") (pinfunction "8_8") (pintype "passive"))
      (node (ref "IC25") (pin "9") (pinfunction "A8_9") (pintype "bidirectional"))
    )
    (net (code "87") (name "PIA-B0") (class "Default")
      (node (ref "CORE-IO") (pin "13") (pinfunction "13_13") (pintype "passive"))
      (node (ref "IC26") (pin "2") (pinfunction "A1_2") (pintype "bidirectional"))
    )
    (net (code "88") (name "PIA-B1") (class "Default")
      (node (ref "CORE-IO") (pin "14") (pinfunction "14_14") (pintype "passive"))
      (node (ref "IC26") (pin "3") (pinfunction "A2_3") (pintype "bidirectional"))
    )
    (net (code "89") (name "PIA-B2") (class "Default")
      (node (ref "CORE-IO") (pin "15") (pinfunction "15_15") (pintype "passive"))
      (node (ref "IC26") (pin "4") (pinfunction "A3_4") (pintype "bidirectional"))
    )
    (net (code "90") (name "PIA-B3") (class "Default")
      (node (ref "CORE-IO") (pin "16") (pinfunction "16_16") (pintype "passive"))
      (node (ref "IC26") (pin "5") (pinfunction "A4_5") (pintype "bidirectional"))
    )
    (net (code "91") (name "PIA-B4") (class "Default")
      (node (ref "CORE-IO") (pin "17") (pinfunction "17_17") (pintype "passive"))
      (node (ref "IC26") (pin "6") (pinfunction "A5_6") (pintype "bidirectional"))
    )
    (net (code "92") (name "PIA-B5") (class "Default")
      (node (ref "CORE-IO") (pin "18") (pinfunction "18_18") (pintype "passive"))
      (node (ref "IC26") (pin "7") (pinfunction "A6_7") (pintype "bidirectional"))
    )
    (net (code "93") (name "PIA-B6") (class "Default")
      (node (ref "CORE-IO") (pin "19") (pinfunction "19_19") (pintype "passive"))
      (node (ref "IC26") (pin "8") (pinfunction "A7_8") (pintype "bidirectional"))
    )
    (net (code "94") (name "PIA-B7") (class "Default")
      (node (ref "CORE-IO") (pin "20") (pinfunction "20_20") (pintype "passive"))
      (node (ref "IC26") (pin "9") (pinfunction "A8_9") (pintype "bidirectional"))
    )
    (net (code "95") (name "Q") (class "Default")
      (node (ref "IC17") (pin "35") (pinfunction "Q_35") (pintype "input"))
      (node (ref "IC2") (pin "12") (pinfunction "Q_12") (pintype "output"))
      (node (ref "IC2") (pin "7") (pinfunction "J_7") (pintype "input"))
    )
    (net (code "96") (name "RX") (class "Default")
      (node (ref "IC20") (pin "12") (pinfunction "R1OUT_12") (pintype "output"))
      (node (ref "IC21") (pin "2") (pinfunction "RXDATA_2") (pintype "input"))
    )
    (net (code "97") (name "RXD") (class "Default")
      (node (ref "COM") (pin "3") (pinfunction "3_3") (pintype "passive"))
      (node (ref "IC20") (pin "13") (pinfunction "R1IN_13") (pintype "input"))
      (node (ref "RS-232") (pin "3") (pinfunction "3_3") (pintype "passive"))
    )
    (net (code "98") (name "R{slash}~{W}") (class "Default")
      (node (ref "EPROM") (pin "5") (pinfunction "5_5") (pintype "passive"))
      (node (ref "IC17") (pin "32") (pinfunction "R/~{W}_32") (pintype "output"))
      (node (ref "IC21") (pin "13") (pinfunction "R/~{W}_13") (pintype "input"))
      (node (ref "IC22") (pin "27") (pinfunction "~{WE}_27") (pintype "input"))
      (node (ref "IC24") (pin "21") (pinfunction "R/~{W}_21") (pintype "input"))
    )
    (net (code "99") (name "TX") (class "Default")
      (node (ref "IC20") (pin "11") (pinfunction "T1IN_11") (pintype "input"))
      (node (ref "IC21") (pin "6") (pinfunction "TXDATA_6") (pintype "output"))
    )
    (net (code "100") (name "TXD") (class "Default")
      (node (ref "COM") (pin "2") (pinfunction "2_2") (pintype "passive"))
      (node (ref "IC20") (pin "14") (pinfunction "T1OUT_14") (pintype "output"))
      (node (ref "RS-232") (pin "1") (pinfunction "1_1") (pintype "passive"))
    )
    (net (code "101") (name "VCC") (class "Default")
      (node (ref "BYP17") (pin "1") (pinfunction "1_1") (pintype "passive"))
      (node (ref "BYP18") (pin "1") (pinfunction "1_1") (pintype "passive"))
      (node (ref "BYP19") (pin "1") (pinfunction "1_1") (pintype "passive"))
      (node (ref "BYP2") (pin "1") (pinfunction "1_1") (pintype "passive"))
      (node (ref "BYP20") (pin "1") (pinfunction "1_1") (pintype "passive"))
      (node (ref "BYP21") (pin "1") (pinfunction "1_1") (pintype "passive"))
      (node (ref "BYP22") (pin "1") (pinfunction "1_1") (pintype "passive"))
      (node (ref "BYP23") (pin "1") (pinfunction "1_1") (pintype "passive"))
      (node (ref "BYP24") (pin "1") (pinfunction "1_1") (pintype "passive"))
      (node (ref "BYP25") (pin "1") (pinfunction "1_1") (pintype "passive"))
      (node (ref "BYP26") (pin "1") (pinfunction "1_1") (pintype "passive"))
      (node (ref "BYP27") (pin "1") (pinfunction "1_1") (pintype "passive"))
      (node (ref "BYP28") (pin "1") (pinfunction "1_1") (pintype "passive"))
      (node (ref "BYP29") (pin "1") (pinfunction "1_1") (pintype "passive"))
      (node (ref "C10") (pin "1") (pinfunction "1_1") (pintype "passive"))
      (node (ref "CORE-IO") (pin "12") (pinfunction "12_12") (pintype "passive"))
      (node (ref "CORE-IO") (pin "9") (pinfunction "9_9") (pintype "passive"))
      (node (ref "DEBUG") (pin "2") (pinfunction "2_2") (pintype "passive"))
      (node (ref "EP-1") (pin "3") (pinfunction "3_3") (pintype "passive"))
      (node (ref "EPROM") (pin "1") (pinfunction "1_1") (pintype "passive"))
      (node (ref "IC17") (pin "7") (pinfunction "VCC_7") (pintype "power_in"))
      (node (ref "IC2") (pin "2") (pinfunction "CL_2") (pintype "input"))
      (node (ref "IC2") (pin "6") (pinfunction "CL_6") (pintype "input"))
      (node (ref "IC21") (pin "10") (pinfunction "CS1_10") (pintype "input"))
      (node (ref "IC21") (pin "12") (pinfunction "VCC_12") (pintype "power_in"))
      (node (ref "IC21") (pin "8") (pinfunction "CS0_8") (pintype "input"))
      (node (ref "IC22") (pin "28") (pinfunction "VCC_28") (pintype "power_in"))
      (node (ref "IC23") (pin "1") (pinfunction "VPP_1") (pintype "input"))
      (node (ref "IC23") (pin "28") (pinfunction "VCC_28") (pintype "power_in"))
      (node (ref "IC24") (pin "20") (pinfunction "VCC_20") (pintype "power_in"))
      (node (ref "IC24") (pin "22") (pinfunction "CS0_22") (pintype "input"))
      (node (ref "IC24") (pin "24") (pinfunction "CS1_24") (pintype "input"))
      (node (ref "IC27") (pin "10") (pinfunction "R_10") (pintype "input"))
      (node (ref "IC27") (pin "14") (pinfunction "V+_14") (pintype "power_in"))
      (node (ref "IC27") (pin "4") (pinfunction "R_4") (pintype "input"))
      (node (ref "JP4") (pin "2") (pinfunction "2_2") (pintype "passive"))
      (node (ref "QG1") (pin "14") (pinfunction "VCC_14") (pintype "power_in"))
      (node (ref "R1") (pin "2") (pinfunction "2_2") (pintype "passive"))
      (node (ref "R12") (pin "2") (pinfunction "2_2") (pintype "passive"))
      (node (ref "R14") (pin "2") (pinfunction "2_2") (pintype "passive"))
      (node (ref "R2") (pin "2") (pinfunction "2_2") (pintype "passive"))
      (node (ref "R3") (pin "2") (pinfunction "2_2") (pintype "passive"))
      (node (ref "R5") (pin "2") (pinfunction "2_2") (pintype "passive"))
      (node (ref "R6") (pin "2") (pinfunction "2_2") (pintype "passive"))
      (node (ref "R7") (pin "2") (pinfunction "2_2") (pintype "passive"))
      (node (ref "R8") (pin "2") (pinfunction "2_2") (pintype "passive"))
      (node (ref "R9") (pin "2") (pinfunction "2_2") (pintype "passive"))
    )
    (net (code "102") (name "unconnected-(COM-Pad1)") (class "Default")
      (node (ref "COM") (pin "1") (pinfunction "1_1") (pintype "passive"))
    )
    (net (code "103") (name "unconnected-(COM-Pad9)") (class "Default")
      (node (ref "COM") (pin "9") (pinfunction "9_9") (pintype "passive"))
    )
    (net (code "104") (name "unconnected-(IC17A-AVMA-Pad36)") (class "Default")
      (node (ref "IC17") (pin "36") (pinfunction "AVMA_36") (pintype "output"))
    )
    (net (code "105") (name "unconnected-(IC17A-BA-Pad6)") (class "Default")
      (node (ref "IC17") (pin "6") (pinfunction "BA_6") (pintype "output"))
    )
    (net (code "106") (name "unconnected-(IC17A-BS-Pad5)") (class "Default")
      (node (ref "IC17") (pin "5") (pinfunction "BS_5") (pintype "output"))
    )
    (net (code "107") (name "unconnected-(IC17A-BUSY-Pad33)") (class "Default")
      (node (ref "IC17") (pin "33") (pinfunction "BUSY_33") (pintype "output"))
    )
    (net (code "108") (name "unconnected-(IC17A-LIC-Pad38)") (class "Default")
      (node (ref "IC17") (pin "38") (pinfunction "LIC_38") (pintype "output"))
    )
    (net (code "109") (name "unconnected-(IC19A-Y0-Pad15)") (class "Default")
      (node (ref "IC19") (pin "15") (pinfunction "Y0_15") (pintype "output"))
    )
    (net (code "110") (name "unconnected-(IC19A-Y1-Pad14)") (class "Default")
      (node (ref "IC19") (pin "14") (pinfunction "Y1_14") (pintype "output"))
    )
    (net (code "111") (name "unconnected-(IC19A-Y2-Pad13)") (class "Default")
      (node (ref "IC19") (pin "13") (pinfunction "Y2_13") (pintype "output"))
    )
    (net (code "112") (name "unconnected-(IC19A-Y3-Pad12)") (class "Default")
      (node (ref "IC19") (pin "12") (pinfunction "Y3_12") (pintype "output"))
    )
    (net (code "113") (name "unconnected-(IC19A-Y4-Pad11)") (class "Default")
      (node (ref "IC19") (pin "11") (pinfunction "Y4_11") (pintype "output"))
    )
    (net (code "114") (name "unconnected-(IC19A-Y5-Pad10)") (class "Default")
      (node (ref "IC19") (pin "10") (pinfunction "Y5_10") (pintype "output"))
    )
    (net (code "115") (name "unconnected-(IC20A-R2OUT-Pad9)") (class "Default")
      (node (ref "IC20") (pin "9") (pinfunction "R2OUT_9") (pintype "output"))
    )
    (net (code "116") (name "unconnected-(IC22-NC-Pad1)") (class "Default")
      (node (ref "IC22") (pin "1") (pinfunction "NC_1") (pintype "no_connect"))
    )
    (net (code "117") (name "unconnected-(IC28A-Y1-Pad5)") (class "Default")
      (node (ref "IC28") (pin "5") (pinfunction "Y1_5") (pintype "output"))
    )
    (net (code "118") (name "unconnected-(IC28A-Y2-Pad6)") (class "Default")
      (node (ref "IC28") (pin "6") (pinfunction "Y2_6") (pintype "output"))
    )
    (net (code "119") (name "unconnected-(IC28B-Y0-Pad12)") (class "Default")
      (node (ref "IC28") (pin "12") (pinfunction "Y0_12") (pintype "output"))
    )
    (net (code "120") (name "~{4-B}") (class "Default")
      (node (ref "IC28") (pin "9") (pinfunction "Y3_9") (pintype "output"))
      (node (ref "IC29") (pin "20") (pinfunction "~{CE}_20") (pintype "input"))
      (node (ref "IC29") (pin "22") (pinfunction "~{OE}_22") (pintype "input"))
    )
    (net (code "121") (name "~{0123}") (class "Default")
      (node (ref "IC19") (pin "5") (pinfunction "G2B_5") (pintype "input"))
      (node (ref "IC22") (pin "20") (pinfunction "~{CS1}_20") (pintype "input"))
      (node (ref "IC22") (pin "22") (pinfunction "~{OE}_22") (pintype "input"))
      (node (ref "IC28") (pin "11") (pinfunction "Y1_11") (pintype "output"))
    )
    (net (code "122") (name "~{CDEF}") (class "Default")
      (node (ref "IC23") (pin "20") (pinfunction "~{CE}_20") (pintype "input"))
      (node (ref "IC23") (pin "22") (pinfunction "~{OE}_22") (pintype "input"))
      (node (ref "IC28") (pin "10") (pinfunction "Y2_10") (pintype "output"))
    )
    (net (code "123") (name "~{EP1}") (class "Default")
      (node (ref "IC28") (pin "14") (pinfunction "A_14") (pintype "input"))
      (node (ref "IC28") (pin "7") (pinfunction "Y3_7") (pintype "output"))
    )
    (net (code "124") (name "~{FIRQ}") (class "Default")
      (node (ref "IC17") (pin "4") (pinfunction "FIRQ_4") (pintype "input"))
      (node (ref "IC24") (pin "37") (pinfunction "IRQB_37") (pintype "open_collector"))
      (node (ref "IC24") (pin "38") (pinfunction "IRQA_38") (pintype "open_collector"))
      (node (ref "R8") (pin "1") (pinfunction "1_1") (pintype "passive"))
    )
    (net (code "125") (name "~{HLT}") (class "Default")
      (node (ref "IC17") (pin "40") (pinfunction "HALT_40") (pintype "input"))
      (node (ref "R5") (pin "1") (pinfunction "1_1") (pintype "passive"))
    )
    (net (code "126") (name "~{IO-E}") (class "Default")
      (node (ref "IC19") (pin "9") (pinfunction "Y6_9") (pintype "output"))
      (node (ref "IC24") (pin "23") (pinfunction "CS2_23") (pintype "input"))
    )
    (net (code "127") (name "~{IO-F}") (class "Default")
      (node (ref "IC19") (pin "7") (pinfunction "Y7_7") (pintype "output"))
      (node (ref "IC21") (pin "9") (pinfunction "CS2_9") (pintype "input"))
    )
    (net (code "128") (name "~{IRQ}") (class "Default")
      (node (ref "IC17") (pin "3") (pinfunction "IRQ_3") (pintype "input"))
      (node (ref "IC21") (pin "7") (pinfunction "IRQ_7") (pintype "output"))
      (node (ref "R7") (pin "1") (pinfunction "1_1") (pintype "passive"))
    )
    (net (code "129") (name "~{NMI}") (class "Default")
      (node (ref "IC17") (pin "2") (pinfunction "NMI_2") (pintype "input"))
      (node (ref "R6") (pin "1") (pinfunction "1_1") (pintype "passive"))
    )
    (net (code "130") (name "~{RST}") (class "Default")
      (node (ref "IC17") (pin "37") (pinfunction "RESET_37") (pintype "input"))
      (node (ref "IC18") (pin "6") (pinfunction "O_6") (pintype "output"))
      (node (ref "IC24") (pin "34") (pinfunction "RESET_34") (pintype "input"))
    )
  )
)
